# sch.net
KiCad netlist of a schematic drawn in Altium Designer
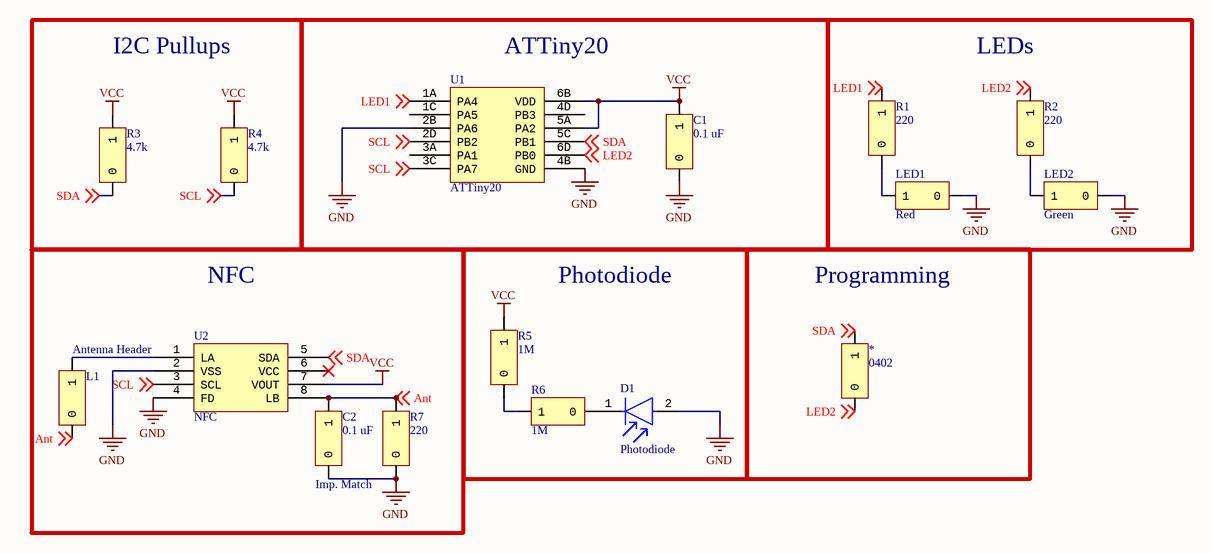
[diagram p0: sch.SchDoc]

(export (version "E")
  (design (tool "Eeschema 10.0.6"))
  (components
    (comp (ref "*")
      (value "0402")
      (footprint "0402")
      (description "0402 Component")
      (libsource (lib "schlib") (part "0402"))
    )
    (comp (ref "C1")
      (value "0.1 uF")
      (footprint "01005")
      (description "01005 Component")
      (fields (field (name "MPN") "CL02A104KQ2NNNC"))
      (libsource (lib "schlib") (part "01005"))
    )
    (comp (ref "C2")
      (value "0.1 uF")
      (footprint "01005")
      (description "01005 Component")
      (fields (field (name "MPN") "CL02A104KQ2NNNC"))
      (libsource (lib "schlib") (part "01005"))
    )
    (comp (ref "D1")
      (value "Photodiode")
      (footprint "FP-6_541-5064_01-4-MFG")
      (description "0805 PHOTODIODE\r\ntemd7000x01")
      (fields
        (field (name "MANUFACTURER") "Vishay")
        (field (name "OCTOPART") "https://octopart.com/temd6200fx01-vishay-19158932")
      )
      (libsource (lib "Altium Content Vault") (part "9b7c99953c265a88c20b8f1023d9605"))
    )
    (comp (ref "L1")
      (value "Antenna Header")
      (footprint "0402")
      (description "0402 Component")
      (libsource (lib "schlib") (part "0402"))
    )
    (comp (ref "LED1")
      (value "Red")
      (footprint "0201")
      (description "0201 Component\r\nXZMDR155W")
      (fields (field (name "MPN") "XZMDR155W"))
      (libsource (lib "schlib") (part "0201"))
    )
    (comp (ref "LED2")
      (value "Green")
      (footprint "0201")
      (description "0201 Component\r\nXZBGR155W5MAV")
      (fields (field (name "MPN") "XZBGR155W5MAV"))
      (libsource (lib "schlib") (part "0201"))
    )
    (comp (ref "R1")
      (value "220")
      (footprint "01005")
      (description "01005 Component\r\nCRCW0100220RFREL")
      (fields (field (name "MPN") "CRCW0100220RFREL"))
      (libsource (lib "schlib") (part "01005"))
    )
    (comp (ref "R2")
      (value "220")
      (footprint "01005")
      (description "01005 Component\r\nCRCW0100220RFREL")
      (fields (field (name "MPN") "CRCW0100220RFREL"))
      (libsource (lib "schlib") (part "01005"))
    )
    (comp (ref "R3")
      (value "4.7k")
      (footprint "01005")
      (description "01005 Component")
      (fields (field (name "MPN") "CL02A104KQ2NNNC"))
      (libsource (lib "schlib") (part "01005"))
    )
    (comp (ref "R4")
      (value "4.7k")
      (footprint "01005")
      (description "01005 Component")
      (fields (field (name "MPN") "CL02A104KQ2NNNC"))
      (libsource (lib "schlib") (part "01005"))
    )
    (comp (ref "R5")
      (value "1M")
      (footprint "01005")
      (description "01005 Component\r\nCRCW01001M00FREL")
      (fields (field (name "MPN") "CRCW01001M00FREL"))
      (libsource (lib "schlib") (part "01005"))
    )
    (comp (ref "R6")
      (value "1M")
      (footprint "01005")
      (description "01005 Component\r\nCRCW01001M00FREL")
      (fields (field (name "MPN") "CRCW01001M00FREL"))
      (libsource (lib "") (part "01005_1"))
    )
    (comp (ref "R7")
      (value "220")
      (footprint "01005")
      (description "01005 Component\r\nCRCW0100220RFREL")
      (fields (field (name "MPN") "CRCW0100220RFREL"))
      (libsource (lib "schlib") (part "01005"))
    )
    (comp (ref "U1") (value "ATTiny20") (footprint "ATTINY10") (libsource (lib "schlib") (part "ATTiny20")))
    (comp (ref "U2") (value "NFC") (footprint "NFC") (libsource (lib "schlib") (part "NFC")))
  )
  (nets
    (net (code "1") (name "Ant") (class "Default")
      (node (ref "C2") (pin "1") (pinfunction "1_1") (pintype "passive"))
      (node (ref "L1") (pin "0") (pinfunction "0_0") (pintype "passive"))
      (node (ref "R7") (pin "1") (pinfunction "1_1") (pintype "passive"))
      (node (ref "U2") (pin "8") (pinfunction "LB_8") (pintype "passive"))
    )
    (net (code "2") (name "GND") (class "Default")
      (node (ref "C1") (pin "0") (pinfunction "0_0") (pintype "passive"))
      (node (ref "C2") (pin "0") (pinfunction "0_0") (pintype "passive"))
      (node (ref "D1") (pin "2") (pinfunction "A_2") (pintype "passive"))
      (node (ref "LED1") (pin "0") (pinfunction "0_0") (pintype "passive"))
      (node (ref "LED2") (pin "0") (pinfunction "0_0") (pintype "passive"))
      (node (ref "R7") (pin "0") (pinfunction "0_0") (pintype "passive"))
      (node (ref "U1") (pin "2B") (pinfunction "PA6_2B") (pintype "passive"))
      (node (ref "U1") (pin "4B") (pinfunction "GND_4B") (pintype "passive"))
      (node (ref "U2") (pin "2") (pinfunction "VSS_2") (pintype "passive"))
      (node (ref "U2") (pin "4") (pinfunction "FD_4") (pintype "passive"))
    )
    (net (code "3") (name "LED1") (class "Default")
      (node (ref "R1") (pin "1") (pinfunction "1_1") (pintype "passive"))
      (node (ref "U1") (pin "1A") (pinfunction "PA4_1A") (pintype "passive"))
    )
    (net (code "4") (name "LED2") (class "Default")
      (node (ref "*") (pin "0") (pinfunction "0_0") (pintype "passive"))
      (node (ref "R2") (pin "1") (pinfunction "1_1") (pintype "passive"))
      (node (ref "U1") (pin "6D") (pinfunction "PB0_6D") (pintype "passive"))
    )
    (net (code "5") (name "Net-(D1-C)") (class "Default")
      (node (ref "D1") (pin "1") (pinfunction "C_1") (pintype "passive"))
      (node (ref "R6") (pin "0") (pinfunction "0_0") (pintype "passive"))
    )
    (net (code "6") (name "Net-(LED1-Pad1)") (class "Default")
      (node (ref "LED1") (pin "1") (pinfunction "1_1") (pintype "passive"))
      (node (ref "R1") (pin "0") (pinfunction "0_0") (pintype "passive"))
    )
    (net (code "7") (name "Net-(LED2-Pad1)") (class "Default")
      (node (ref "LED2") (pin "1") (pinfunction "1_1") (pintype "passive"))
      (node (ref "R2") (pin "0") (pinfunction "0_0") (pintype "passive"))
    )
    (net (code "8") (name "Net-(R5-Pad0)") (class "Default")
      (node (ref "R5") (pin "0") (pinfunction "0_0") (pintype "passive"))
      (node (ref "R6") (pin "1") (pinfunction "1_1") (pintype "passive"))
    )
    (net (code "9") (name "Net-(U2-LA)") (class "Default")
      (node (ref "L1") (pin "1") (pinfunction "1_1") (pintype "passive"))
      (node (ref "U2") (pin "1") (pinfunction "LA_1") (pintype "passive"))
    )
    (net (code "10") (name "SCL") (class "Default")
      (node (ref "R4") (pin "0") (pinfunction "0_0") (pintype "passive"))
      (node (ref "U1") (pin "2D") (pinfunction "PB2_2D") (pintype "passive"))
      (node (ref "U1") (pin "3C") (pinfunction "PA7_3C") (pintype "passive"))
      (node (ref "U2") (pin "3") (pinfunction "SCL_3") (pintype "passive"))
    )
    (net (code "11") (name "SDA") (class "Default")
      (node (ref "*") (pin "1") (pinfunction "1_1") (pintype "passive"))
      (node (ref "R3") (pin "0") (pinfunction "0_0") (pintype "passive"))
      (node (ref "U1") (pin "5C") (pinfunction "PB1_5C") (pintype "passive"))
      (node (ref "U2") (pin "5") (pinfunction "SDA_5") (pintype "passive"))
    )
    (net (code "12") (name "VCC") (class "Default")
      (node (ref "C1") (pin "1") (pinfunction "1_1") (pintype "passive"))
      (node (ref "R3") (pin "1") (pinfunction "1_1") (pintype "passive"))
      (node (ref "R4") (pin "1") (pinfunction "1_1") (pintype "passive"))
      (node (ref "R5") (pin "1") (pinfunction "1_1") (pintype "passive"))
      (node (ref "U1") (pin "5A") (pinfunction "PA2_5A") (pintype "passive"))
      (node (ref "U1") (pin "6B") (pinfunction "VDD_6B") (pintype "passive"))
      (node (ref "U2") (pin "7") (pinfunction "VOUT_7") (pintype "passive"))
    )
    (net (code "13") (name "unconnected-(U1-PA1-Pad3A)") (class "Default")
      (node (ref "U1") (pin "3A") (pinfunction "PA1_3A") (pintype "passive"))
    )
    (net (code "14") (name "unconnected-(U1-PA5-Pad1C)") (class "Default")
      (node (ref "U1") (pin "1C") (pinfunction "PA5_1C") (pintype "passive"))
    )
    (net (code "15") (name "unconnected-(U1-PB3-Pad4D)") (class "Default")
      (node (ref "U1") (pin "4D") (pinfunction "PB3_4D") (pintype "passive"))
    )
    (net (code "16") (name "unconnected-(U2-VCC-Pad6)") (class "Default")
      (node (ref "U2") (pin "6") (pinfunction "VCC_6") (pintype "passive+no_connect"))
    )
  )
)
